# STorM32_NT_BGC_v332m_sz2u.net
KiCad netlist of a schematic drawn in EAGLE
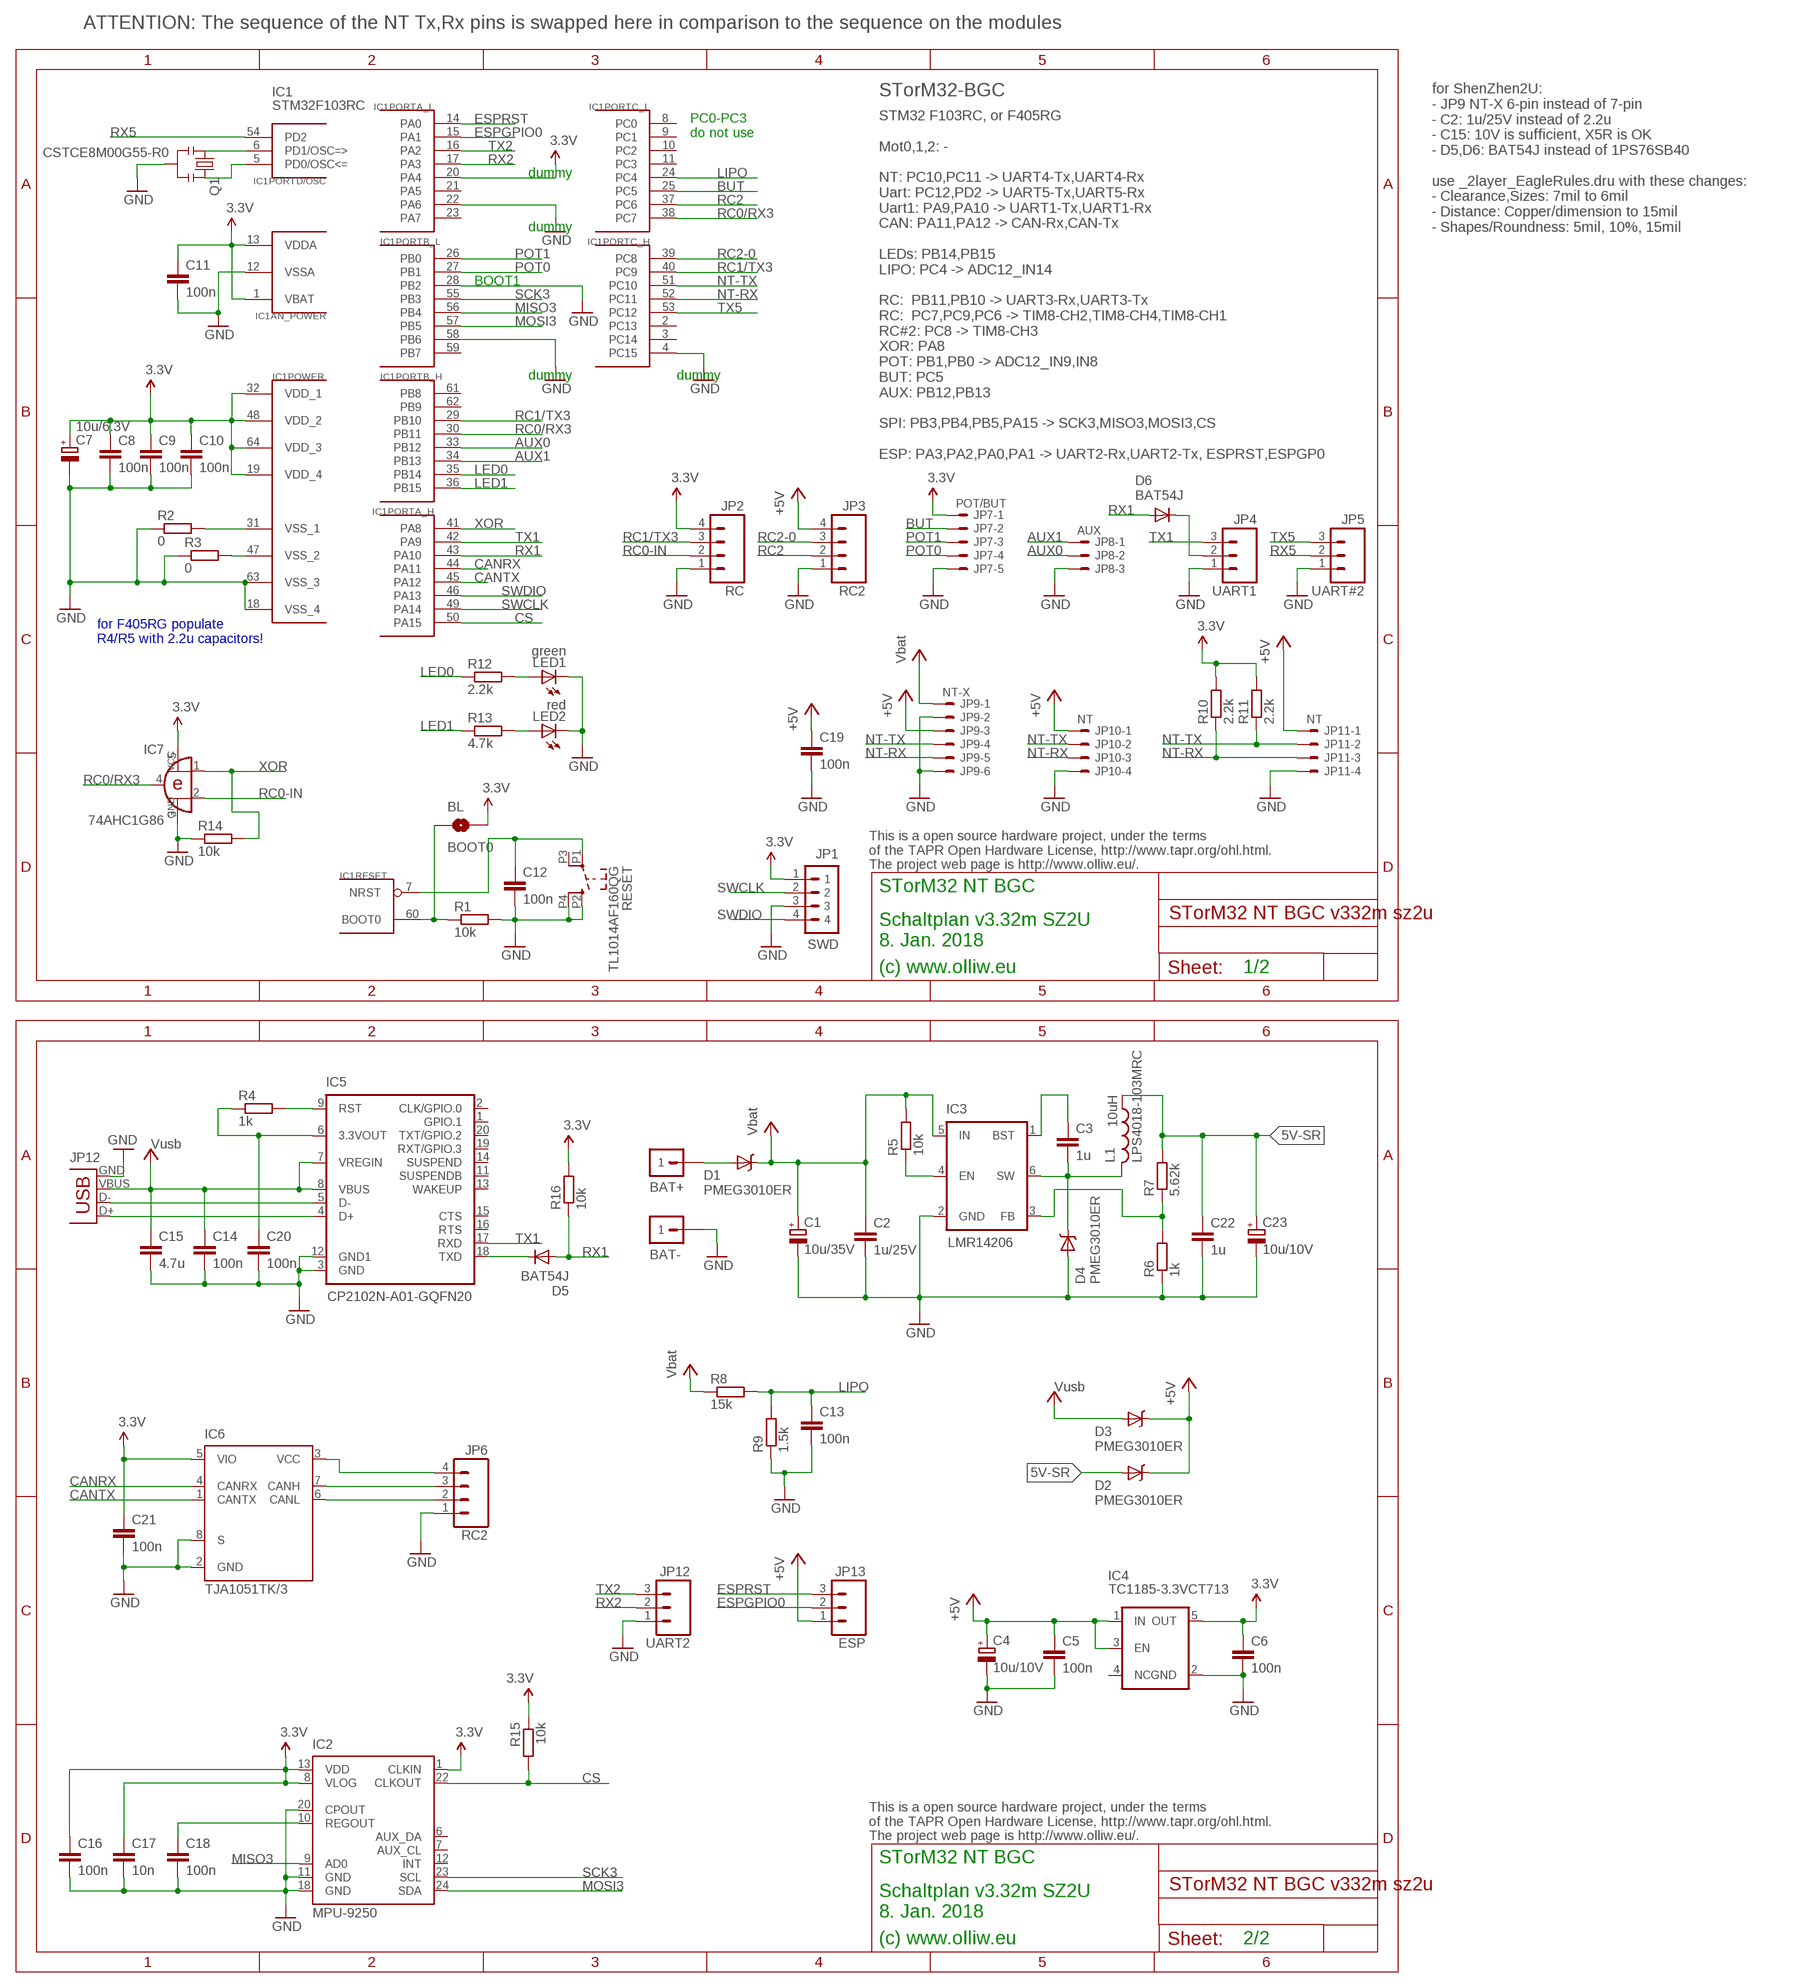
[diagram p0: schematic, sheet 1]

(export (version "E")
  (design (tool "Eeschema 10.0.6"))
  (components
    (comp (ref "BAT+")
      (value "M1X1")
      (footprint "eagle-import:1X1_WITHOUT")
      (libsource (lib "eagle-import") (part "M1X1"))
    )
    (comp (ref "BAT-")
      (value "M1X1")
      (footprint "eagle-import:1X1_WITHOUT")
      (libsource (lib "eagle-import") (part "M1X1"))
    )
    (comp (ref "BL")
      (value "BOOT0")
      (footprint "eagle-import:SJ_2S-NO")
      (libsource (lib "eagle-import") (part "SOLDERJUMPERNO"))
    )
    (comp (ref "C1")
      (value "10u/35V")
      (footprint "eagle-import:SMC_B")
      (libsource (lib "eagle-import") (part "CPOL-EUSMCB"))
    )
    (comp (ref "C2")
      (value "1u/25V")
      (footprint "eagle-import:C0603")
      (libsource (lib "eagle-import") (part "C-EUC0603"))
    )
    (comp (ref "C3")
      (value "1u")
      (footprint "eagle-import:C0603")
      (libsource (lib "eagle-import") (part "C-EUC0603"))
    )
    (comp (ref "C4")
      (value "10u/10V")
      (footprint "eagle-import:SMC_A")
      (libsource (lib "eagle-import") (part "CPOL-EUSMCA"))
    )
    (comp (ref "C5")
      (value "100n")
      (footprint "eagle-import:C0603")
      (libsource (lib "eagle-import") (part "C-EUC0603"))
    )
    (comp (ref "C6")
      (value "100n")
      (footprint "eagle-import:C0402")
      (libsource (lib "eagle-import") (part "C-EUC0402"))
    )
    (comp (ref "C7")
      (value "10u/6.3V")
      (footprint "eagle-import:SMC_A")
      (libsource (lib "eagle-import") (part "CPOL-EUSMCA"))
    )
    (comp (ref "C8")
      (value "100n")
      (footprint "eagle-import:C0402")
      (libsource (lib "eagle-import") (part "C-EUC0402"))
    )
    (comp (ref "C9")
      (value "100n")
      (footprint "eagle-import:C0402")
      (libsource (lib "eagle-import") (part "C-EUC0402"))
    )
    (comp (ref "C10")
      (value "100n")
      (footprint "eagle-import:C0402")
      (libsource (lib "eagle-import") (part "C-EUC0402"))
    )
    (comp (ref "C11")
      (value "100n")
      (footprint "eagle-import:C0402")
      (libsource (lib "eagle-import") (part "C-EUC0402"))
    )
    (comp (ref "C12")
      (value "100n")
      (footprint "eagle-import:C0402")
      (libsource (lib "eagle-import") (part "C-EUC0402"))
    )
    (comp (ref "C13")
      (value "100n")
      (footprint "eagle-import:C0402")
      (libsource (lib "eagle-import") (part "C-EUC0402"))
    )
    (comp (ref "C14")
      (value "100n")
      (footprint "eagle-import:C0402")
      (libsource (lib "eagle-import") (part "C-EUC0402"))
    )
    (comp (ref "C15")
      (value "4.7u")
      (footprint "eagle-import:C0603")
      (libsource (lib "eagle-import") (part "C-EUC0603"))
    )
    (comp (ref "C16")
      (value "100n")
      (footprint "eagle-import:C0402")
      (libsource (lib "eagle-import") (part "C-EUC0402"))
    )
    (comp (ref "C17")
      (value "10n")
      (footprint "eagle-import:C0402")
      (libsource (lib "eagle-import") (part "C-EUC0402"))
    )
    (comp (ref "C18")
      (value "100n")
      (footprint "eagle-import:C0402")
      (libsource (lib "eagle-import") (part "C-EUC0402"))
    )
    (comp (ref "C19")
      (value "100n")
      (footprint "eagle-import:C0402")
      (libsource (lib "eagle-import") (part "C-EUC0402"))
    )
    (comp (ref "C20")
      (value "100n")
      (footprint "eagle-import:C0402")
      (libsource (lib "eagle-import") (part "C-EUC0402"))
    )
    (comp (ref "C21")
      (value "100n")
      (footprint "eagle-import:C0402")
      (libsource (lib "eagle-import") (part "C-EUC0402"))
    )
    (comp (ref "C22")
      (value "1u")
      (footprint "eagle-import:C0603")
      (libsource (lib "eagle-import") (part "C-EUC0603"))
    )
    (comp (ref "C23")
      (value "10u/10V")
      (footprint "eagle-import:SMC_A")
      (libsource (lib "eagle-import") (part "CPOL-EUSMCA"))
    )
    (comp (ref "D1")
      (value "PMEG3010ER")
      (footprint "eagle-import:SOD123W-DIODE")
      (libsource (lib "eagle-import") (part "DIODE-SCHOTTKYSOD123-W"))
    )
    (comp (ref "D2")
      (value "PMEG3010ER")
      (footprint "eagle-import:SOD123W-DIODE")
      (libsource (lib "eagle-import") (part "DIODE-SCHOTTKYSOD123-W"))
    )
    (comp (ref "D3")
      (value "PMEG3010ER")
      (footprint "eagle-import:SOD123W-DIODE")
      (libsource (lib "eagle-import") (part "DIODE-SCHOTTKYSOD123-W"))
    )
    (comp (ref "D4")
      (value "PMEG3010ER")
      (footprint "eagle-import:SOD123W-DIODE")
      (libsource (lib "eagle-import") (part "DIODE-SCHOTTKYSOD123-W"))
    )
    (comp (ref "D5")
      (value "BAT54J")
      (footprint "eagle-import:SOD110-R")
      (libsource (lib "eagle-import") (part "DIODE-SOD110-R"))
    )
    (comp (ref "D6")
      (value "BAT54J")
      (footprint "eagle-import:SOD110-R")
      (libsource (lib "eagle-import") (part "DIODE-SOD110-R"))
    )
    (comp (ref "IC1")
      (value "STM32F103RCT6")
      (footprint "eagle-import:TQFP64")
      (libsource (lib "eagle-import") (part "STM32F10XRXT6"))
    )
    (comp (ref "IC2")
      (value "MPU-9250")
      (footprint "eagle-import:QFN-24-3X3")
      (libsource (lib "eagle-import") (part "IMU3000QFN-24-0.4MIL"))
    )
    (comp (ref "IC3")
      (value "LMR14206")
      (footprint "eagle-import:SOT23-6")
      (libsource (lib "eagle-import") (part "MP2359"))
    )
    (comp (ref "IC4")
      (value "TC1185-3.3VCT713")
      (footprint "eagle-import:SOT23-5")
      (libsource (lib "eagle-import") (part "V_REG_TPS76433SOT23-5"))
    )
    (comp (ref "IC5")
      (value "CP2102N-A01-GQFN20")
      (footprint "eagle-import:QFN20-CP2102N")
      (libsource (lib "eagle-import") (part "CP2102N-QFN20"))
    )
    (comp (ref "IC6")
      (value "TJA1051TK/3")
      (footprint "eagle-import:HVSON8")
      (libsource (lib "eagle-import") (part "TJA1051TK/3"))
    )
    (comp (ref "IC7")
      (value "74AHC1G86")
      (footprint "eagle-import:SOT23-5-VER1")
      (libsource (lib "eagle-import") (part "74AHC1G86"))
    )
    (comp (ref "JP1")
      (value "SWD")
      (footprint "eagle-import:4X1_1P27_OCT_BILEX")
      (libsource (lib "eagle-import") (part "P4X1_1P27-OCT_BILEX"))
    )
    (comp (ref "JP2")
      (value "RC")
      (footprint "eagle-import:1X04_NO_SILK")
      (libsource (lib "eagle-import") (part "M041X04_NO_SILK"))
    )
    (comp (ref "JP3")
      (value "RC2")
      (footprint "eagle-import:1X04_NO_SILK")
      (libsource (lib "eagle-import") (part "M041X04_NO_SILK"))
    )
    (comp (ref "JP4")
      (value "UART1")
      (footprint "eagle-import:1X03_NO_SILK")
      (libsource (lib "eagle-import") (part "M031X03_NO_SILK"))
    )
    (comp (ref "JP5")
      (value "UART#2")
      (footprint "eagle-import:1X03_NO_SILK")
      (libsource (lib "eagle-import") (part "M031X03_NO_SILK"))
    )
    (comp (ref "JP6")
      (value "RC2")
      (footprint "eagle-import:1X04_NO_SILK")
      (libsource (lib "eagle-import") (part "M041X04_NO_SILK"))
    )
    (comp (ref "JP7")
      (value "POT/BUT")
      (footprint "eagle-import:SM05B-SRSS-TB")
      (libsource (lib "eagle-import") (part "?M05B-SRSS-TBS"))
    )
    (comp (ref "JP8")
      (value "AUX")
      (footprint "eagle-import:SM03B-SRSS-TB")
      (libsource (lib "eagle-import") (part "?M03B-SRSS-TBS"))
    )
    (comp (ref "JP9")
      (value "NT-X")
      (footprint "eagle-import:SM06B-SRSS-TB")
      (libsource (lib "eagle-import") (part "?M06B-SRSS-TBS"))
    )
    (comp (ref "JP10")
      (value "NT")
      (footprint "eagle-import:SM04B-SRSS-TB")
      (libsource (lib "eagle-import") (part "?M04B-SRSS-TBS"))
    )
    (comp (ref "JP11")
      (value "NT")
      (footprint "eagle-import:SM04B-SRSS-TB")
      (libsource (lib "eagle-import") (part "?M04B-SRSS-TBS"))
    )
    (comp (ref "JP12")
      (value "UART2")
      (footprint "eagle-import:1X03_NO_SILK")
      (libsource (lib "eagle-import") (part "M031X03_NO_SILK"))
    )
    (comp (ref "JP13")
      (value "ESP")
      (footprint "eagle-import:1X03_NO_SILK")
      (libsource (lib "eagle-import") (part "M031X03_NO_SILK"))
    )
    (comp (ref "L1")
      (value "LPS4018-103MRC")
      (footprint "eagle-import:L4X4")
      (libsource (lib "eagle-import") (part "L"))
    )
    (comp (ref "LED1")
      (value "green")
      (footprint "eagle-import:CHIPLED_0603")
      (libsource (lib "eagle-import") (part "LEDCHIPLED_0603"))
    )
    (comp (ref "LED2")
      (value "red")
      (footprint "eagle-import:CHIPLED_0603")
      (libsource (lib "eagle-import") (part "LEDCHIPLED_0603"))
    )
    (comp (ref "Q1")
      (value "CSTCE8M00G55-R0")
      (footprint "eagle-import:RESONATOR-SMD")
      (libsource (lib "eagle-import") (part "RESONATORSMD"))
    )
    (comp (ref "R1")
      (value "10k")
      (footprint "eagle-import:R0402")
      (libsource (lib "eagle-import") (part "R-EU_R0402"))
    )
    (comp (ref "R2")
      (value "0")
      (footprint "eagle-import:R0402")
      (libsource (lib "eagle-import") (part "R-EU_R0402"))
    )
    (comp (ref "R3")
      (value "0")
      (footprint "eagle-import:R0402")
      (libsource (lib "eagle-import") (part "R-EU_R0402"))
    )
    (comp (ref "R4")
      (value "1k")
      (footprint "eagle-import:R0402")
      (libsource (lib "eagle-import") (part "R-EU_R0402"))
    )
    (comp (ref "R5")
      (value "10k")
      (footprint "eagle-import:R0402")
      (libsource (lib "eagle-import") (part "R-EU_R0402"))
    )
    (comp (ref "R6")
      (value "1k")
      (footprint "eagle-import:R0402")
      (libsource (lib "eagle-import") (part "R-EU_R0402"))
    )
    (comp (ref "R7")
      (value "5.62k")
      (footprint "eagle-import:R0402")
      (libsource (lib "eagle-import") (part "R-EU_R0402"))
    )
    (comp (ref "R8")
      (value "15k")
      (footprint "eagle-import:R0402")
      (libsource (lib "eagle-import") (part "R-EU_R0402"))
    )
    (comp (ref "R9")
      (value "1.5k")
      (footprint "eagle-import:R0402")
      (libsource (lib "eagle-import") (part "R-EU_R0402"))
    )
    (comp (ref "R10")
      (value "2.2k")
      (footprint "eagle-import:R0402")
      (libsource (lib "eagle-import") (part "R-EU_R0402"))
    )
    (comp (ref "R11")
      (value "2.2k")
      (footprint "eagle-import:R0402")
      (libsource (lib "eagle-import") (part "R-EU_R0402"))
    )
    (comp (ref "R12")
      (value "2.2k")
      (footprint "eagle-import:R0402")
      (libsource (lib "eagle-import") (part "R-EU_R0402"))
    )
    (comp (ref "R13")
      (value "4.7k")
      (footprint "eagle-import:R0402")
      (libsource (lib "eagle-import") (part "R-EU_R0402"))
    )
    (comp (ref "R14")
      (value "10k")
      (footprint "eagle-import:R0402")
      (libsource (lib "eagle-import") (part "R-EU_R0402"))
    )
    (comp (ref "R15")
      (value "10k")
      (footprint "eagle-import:R0402")
      (libsource (lib "eagle-import") (part "R-EU_R0402"))
    )
    (comp (ref "R16")
      (value "10k")
      (footprint "eagle-import:R0402")
      (libsource (lib "eagle-import") (part "R-EU_R0402"))
    )
    (comp (ref "RESET")
      (value "TL1014AF160QG")
      (footprint "eagle-import:TACTILE-SWITCH-SMD-RIGHT-TL1014")
      (libsource (lib "eagle-import") (part "SWITCH-SMD-RIGHT-TL1014"))
    )
    (comp (ref "USB")
      (value "Amphenol 10118192-0001LF")
      (footprint "eagle-import:USB-MICROB")
      (libsource (lib "eagle-import") (part "USB-MICROB"))
    )
  )
  (nets
    (net (code "1") (name "+5V") (class "Default")
      (node (ref "C19") (pin "1") (pinfunction "1_1") (pintype "passive"))
      (node (ref "C4") (pin "+") (pinfunction "+_+") (pintype "passive"))
      (node (ref "C5") (pin "1") (pinfunction "1_1") (pintype "passive"))
      (node (ref "D2") (pin "C") (pinfunction "C_C") (pintype "passive"))
      (node (ref "D3") (pin "C") (pinfunction "C_C") (pintype "passive"))
      (node (ref "IC4") (pin "1") (pinfunction "IN_1") (pintype "power_in"))
      (node (ref "IC4") (pin "3") (pinfunction "EN_3") (pintype "input"))
      (node (ref "JP10") (pin "1") (pinfunction "S_1") (pintype "passive"))
      (node (ref "JP11") (pin "1") (pinfunction "S_1") (pintype "passive"))
      (node (ref "JP13") (pin "1") (pinfunction "1_1") (pintype "passive"))
      (node (ref "JP3") (pin "4") (pinfunction "4_4") (pintype "passive"))
      (node (ref "JP9") (pin "3") (pinfunction "S_3") (pintype "passive"))
    )
    (net (code "2") (name "/AUX0") (class "Default")
      (node (ref "IC1") (pin "33") (pinfunction "PB12_33") (pintype "bidirectional"))
      (node (ref "JP8") (pin "2") (pinfunction "S_2") (pintype "passive"))
    )
    (net (code "3") (name "/AUX1") (class "Default")
      (node (ref "IC1") (pin "34") (pinfunction "PB13_34") (pintype "bidirectional"))
      (node (ref "JP8") (pin "1") (pinfunction "S_1") (pintype "passive"))
    )
    (net (code "4") (name "/BUT") (class "Default")
      (node (ref "IC1") (pin "25") (pinfunction "PC5_25") (pintype "bidirectional"))
      (node (ref "JP7") (pin "2") (pinfunction "S_2") (pintype "passive"))
    )
    (net (code "5") (name "/CANRX") (class "Default")
      (node (ref "IC1") (pin "44") (pinfunction "PA11_44") (pintype "bidirectional"))
      (node (ref "IC6") (pin "4") (pinfunction "CANRX_4") (pintype "output"))
    )
    (net (code "6") (name "/CANTX") (class "Default")
      (node (ref "IC1") (pin "45") (pinfunction "PA12_45") (pintype "bidirectional"))
      (node (ref "IC6") (pin "1") (pinfunction "CANTX_1") (pintype "input"))
    )
    (net (code "7") (name "/CS") (class "Default")
      (node (ref "IC1") (pin "50") (pinfunction "PA15_50") (pintype "bidirectional"))
      (node (ref "IC2") (pin "22") (pinfunction "CLKOUT_22") (pintype "bidirectional"))
      (node (ref "R15") (pin "2") (pinfunction "2_2") (pintype "passive"))
    )
    (net (code "8") (name "/ESPGPIO0") (class "Default")
      (node (ref "IC1") (pin "15") (pinfunction "PA1_15") (pintype "bidirectional"))
      (node (ref "JP13") (pin "2") (pinfunction "2_2") (pintype "passive"))
    )
    (net (code "9") (name "/ESPRST") (class "Default")
      (node (ref "IC1") (pin "14") (pinfunction "PA0_14") (pintype "bidirectional"))
      (node (ref "JP13") (pin "3") (pinfunction "3_3") (pintype "passive"))
    )
    (net (code "10") (name "/LED0") (class "Default")
      (node (ref "IC1") (pin "35") (pinfunction "PB14_35") (pintype "bidirectional"))
      (node (ref "R12") (pin "1") (pinfunction "1_1") (pintype "passive"))
    )
    (net (code "11") (name "/LED1") (class "Default")
      (node (ref "IC1") (pin "36") (pinfunction "PB15_36") (pintype "bidirectional"))
      (node (ref "R13") (pin "1") (pinfunction "1_1") (pintype "passive"))
    )
    (net (code "12") (name "/LIPO") (class "Default")
      (node (ref "C13") (pin "1") (pinfunction "1_1") (pintype "passive"))
      (node (ref "IC1") (pin "24") (pinfunction "PC4_24") (pintype "bidirectional"))
      (node (ref "R8") (pin "2") (pinfunction "2_2") (pintype "passive"))
      (node (ref "R9") (pin "2") (pinfunction "2_2") (pintype "passive"))
    )
    (net (code "13") (name "/MISO3") (class "Default")
      (node (ref "IC1") (pin "56") (pinfunction "PB4_56") (pintype "bidirectional"))
      (node (ref "IC2") (pin "9") (pinfunction "AD0_9") (pintype "bidirectional"))
    )
    (net (code "14") (name "/MOSI3") (class "Default")
      (node (ref "IC1") (pin "57") (pinfunction "PB5_57") (pintype "bidirectional"))
      (node (ref "IC2") (pin "24") (pinfunction "SDA_24") (pintype "bidirectional"))
    )
    (net (code "15") (name "/NT-RX") (class "Default")
      (node (ref "IC1") (pin "52") (pinfunction "PC11_52") (pintype "bidirectional"))
      (node (ref "JP10") (pin "3") (pinfunction "S_3") (pintype "passive"))
      (node (ref "JP11") (pin "3") (pinfunction "S_3") (pintype "passive"))
      (node (ref "JP9") (pin "5") (pinfunction "S_5") (pintype "passive"))
      (node (ref "R10") (pin "1") (pinfunction "1_1") (pintype "passive"))
    )
    (net (code "16") (name "/NT-TX") (class "Default")
      (node (ref "IC1") (pin "51") (pinfunction "PC10_51") (pintype "bidirectional"))
      (node (ref "JP10") (pin "2") (pinfunction "S_2") (pintype "passive"))
      (node (ref "JP11") (pin "2") (pinfunction "S_2") (pintype "passive"))
      (node (ref "JP9") (pin "4") (pinfunction "S_4") (pintype "passive"))
      (node (ref "R11") (pin "1") (pinfunction "1_1") (pintype "passive"))
    )
    (net (code "17") (name "/POT0") (class "Default")
      (node (ref "IC1") (pin "27") (pinfunction "PB1_27") (pintype "bidirectional"))
      (node (ref "JP7") (pin "4") (pinfunction "S_4") (pintype "passive"))
    )
    (net (code "18") (name "/POT1") (class "Default")
      (node (ref "IC1") (pin "26") (pinfunction "PB0_26") (pintype "bidirectional"))
      (node (ref "JP7") (pin "3") (pinfunction "S_3") (pintype "passive"))
    )
    (net (code "19") (name "/RC0-IN") (class "Default")
      (node (ref "IC7") (pin "2") (pinfunction "I1_2") (pintype "input"))
      (node (ref "JP2") (pin "2") (pinfunction "2_2") (pintype "passive"))
    )
    (net (code "20") (name "/RC0{slash}RX3") (class "Default")
      (node (ref "IC1") (pin "30") (pinfunction "PB11_30") (pintype "bidirectional"))
      (node (ref "IC1") (pin "38") (pinfunction "PC7_38") (pintype "bidirectional"))
      (node (ref "IC7") (pin "4") (pinfunction "O_4") (pintype "output"))
    )
    (net (code "21") (name "/RC1{slash}TX3") (class "Default")
      (node (ref "IC1") (pin "29") (pinfunction "PB10_29") (pintype "bidirectional"))
      (node (ref "IC1") (pin "40") (pinfunction "PC9_40") (pintype "bidirectional"))
      (node (ref "JP2") (pin "3") (pinfunction "3_3") (pintype "passive"))
    )
    (net (code "22") (name "/RC2") (class "Default")
      (node (ref "IC1") (pin "37") (pinfunction "PC6_37") (pintype "bidirectional"))
      (node (ref "JP3") (pin "2") (pinfunction "2_2") (pintype "passive"))
    )
    (net (code "23") (name "/RC2-0") (class "Default")
      (node (ref "IC1") (pin "39") (pinfunction "PC8_39") (pintype "bidirectional"))
      (node (ref "JP3") (pin "3") (pinfunction "3_3") (pintype "passive"))
    )
    (net (code "24") (name "/RX1") (class "Default")
      (node (ref "D5") (pin "A") (pinfunction "A_A") (pintype "passive"))
      (node (ref "D6") (pin "A") (pinfunction "A_A") (pintype "passive"))
      (node (ref "IC1") (pin "43") (pinfunction "PA10_43") (pintype "bidirectional"))
      (node (ref "R16") (pin "1") (pinfunction "1_1") (pintype "passive"))
    )
    (net (code "25") (name "/RX2") (class "Default")
      (node (ref "IC1") (pin "17") (pinfunction "PA3_17") (pintype "bidirectional"))
      (node (ref "JP12") (pin "2") (pinfunction "2_2") (pintype "passive"))
    )
    (net (code "26") (name "/RX5") (class "Default")
      (node (ref "IC1") (pin "54") (pinfunction "PD2_54") (pintype "bidirectional"))
      (node (ref "JP5") (pin "2") (pinfunction "2_2") (pintype "passive"))
    )
    (net (code "27") (name "/SCK3") (class "Default")
      (node (ref "IC1") (pin "55") (pinfunction "PB3_55") (pintype "bidirectional"))
      (node (ref "IC2") (pin "23") (pinfunction "SCL_23") (pintype "bidirectional"))
    )
    (net (code "28") (name "/SWCLK") (class "Default")
      (node (ref "IC1") (pin "49") (pinfunction "PA14_49") (pintype "bidirectional"))
      (node (ref "JP1") (pin "2") (pinfunction "2_2") (pintype "passive"))
    )
    (net (code "29") (name "/SWDIO") (class "Default")
      (node (ref "IC1") (pin "46") (pinfunction "PA13_46") (pintype "bidirectional"))
      (node (ref "JP1") (pin "4") (pinfunction "4_4") (pintype "passive"))
    )
    (net (code "30") (name "/TX1") (class "Default")
      (node (ref "IC1") (pin "42") (pinfunction "PA9_42") (pintype "bidirectional"))
      (node (ref "IC5") (pin "17") (pinfunction "RXD_17") (pintype "input"))
      (node (ref "JP4") (pin "3") (pinfunction "3_3") (pintype "passive"))
    )
    (net (code "31") (name "/TX2") (class "Default")
      (node (ref "IC1") (pin "16") (pinfunction "PA2_16") (pintype "bidirectional"))
      (node (ref "JP12") (pin "3") (pinfunction "3_3") (pintype "passive"))
    )
    (net (code "32") (name "/TX5") (class "Default")
      (node (ref "IC1") (pin "53") (pinfunction "PC12_53") (pintype "bidirectional"))
      (node (ref "JP5") (pin "3") (pinfunction "3_3") (pintype "passive"))
    )
    (net (code "33") (name "/XOR") (class "Default")
      (node (ref "IC1") (pin "41") (pinfunction "PA8_41") (pintype "bidirectional"))
      (node (ref "IC7") (pin "1") (pinfunction "I0_1") (pintype "input"))
      (node (ref "R14") (pin "2") (pinfunction "2_2") (pintype "passive"))
    )
    (net (code "34") (name "3.3V") (class "Default")
      (node (ref "BL") (pin "2") (pinfunction "2_2") (pintype "passive"))
      (node (ref "C10") (pin "1") (pinfunction "1_1") (pintype "passive"))
      (node (ref "C11") (pin "1") (pinfunction "1_1") (pintype "passive"))
      (node (ref "C16") (pin "1") (pinfunction "1_1") (pintype "passive"))
      (node (ref "C17") (pin "1") (pinfunction "1_1") (pintype "passive"))
      (node (ref "C21") (pin "1") (pinfunction "1_1") (pintype "passive"))
      (node (ref "C6") (pin "1") (pinfunction "1_1") (pintype "passive"))
      (node (ref "C7") (pin "+") (pinfunction "+_+") (pintype "passive"))
      (node (ref "C8") (pin "1") (pinfunction "1_1") (pintype "passive"))
      (node (ref "C9") (pin "1") (pinfunction "1_1") (pintype "passive"))
      (node (ref "IC1") (pin "1") (pinfunction "VBAT_1") (pintype "power_in"))
      (node (ref "IC1") (pin "13") (pinfunction "VDDA_13") (pintype "power_in"))
      (node (ref "IC1") (pin "19") (pinfunction "VDD_4_19") (pintype "power_in"))
      (node (ref "IC1") (pin "20") (pinfunction "PA4_20") (pintype "bidirectional"))
      (node (ref "IC1") (pin "32") (pinfunction "VDD_1_32") (pintype "power_in"))
      (node (ref "IC1") (pin "48") (pinfunction "VDD_2_48") (pintype "power_in"))
      (node (ref "IC1") (pin "64") (pinfunction "VDD_3_64") (pintype "power_in"))
      (node (ref "IC2") (pin "1") (pinfunction "CLKIN_1") (pintype "bidirectional"))
      (node (ref "IC2") (pin "13") (pinfunction "VDD_13") (pintype "bidirectional"))
      (node (ref "IC2") (pin "8") (pinfunction "VLOG_8") (pintype "bidirectional"))
      (node (ref "IC4") (pin "5") (pinfunction "OUT_5") (pintype "output"))
      (node (ref "IC6") (pin "5") (pinfunction "VIO_5") (pintype "power_in"))
      (node (ref "IC7") (pin "5") (pinfunction "VCC_5") (pintype "power_in"))
      (node (ref "JP1") (pin "1") (pinfunction "1_1") (pintype "passive"))
      (node (ref "JP2") (pin "4") (pinfunction "4_4") (pintype "passive"))
      (node (ref "JP7") (pin "1") (pinfunction "S_1") (pintype "passive"))
      (node (ref "R10") (pin "2") (pinfunction "2_2") (pintype "passive"))
      (node (ref "R11") (pin "2") (pinfunction "2_2") (pintype "passive"))
      (node (ref "R15") (pin "1") (pinfunction "1_1") (pintype "passive"))
      (node (ref "R16") (pin "2") (pinfunction "2_2") (pintype "passive"))
    )
    (net (code "35") (name "5V-SR") (class "Default")
      (node (ref "C22") (pin "1") (pinfunction "1_1") (pintype "passive"))
      (node (ref "C23") (pin "+") (pinfunction "+_+") (pintype "passive"))
      (node (ref "D2") (pin "A") (pinfunction "A_A") (pintype "passive"))
      (node (ref "L1") (pin "1") (pinfunction "1_1") (pintype "passive"))
      (node (ref "R7") (pin "2") (pinfunction "2_2") (pintype "passive"))
    )
    (net (code "36") (name "GND") (class "Default")
      (node (ref "BAT-") (pin "1") (pinfunction "1_1") (pintype "passive"))
      (node (ref "C1") (pin "-") (pinfunction "-_-") (pintype "passive"))
      (node (ref "C10") (pin "2") (pinfunction "2_2") (pintype "passive"))
      (node (ref "C11") (pin "2") (pinfunction "2_2") (pintype "passive"))
      (node (ref "C12") (pin "2") (pinfunction "2_2") (pintype "passive"))
      (node (ref "C13") (pin "2") (pinfunction "2_2") (pintype "passive"))
      (node (ref "C14") (pin "2") (pinfunction "2_2") (pintype "passive"))
      (node (ref "C15") (pin "2") (pinfunction "2_2") (pintype "passive"))
      (node (ref "C16") (pin "2") (pinfunction "2_2") (pintype "passive"))
      (node (ref "C17") (pin "2") (pinfunction "2_2") (pintype "passive"))
      (node (ref "C18") (pin "2") (pinfunction "2_2") (pintype "passive"))
      (node (ref "C19") (pin "2") (pinfunction "2_2") (pintype "passive"))
      (node (ref "C2") (pin "2") (pinfunction "2_2") (pintype "passive"))
      (node (ref "C20") (pin "2") (pinfunction "2_2") (pintype "passive"))
      (node (ref "C21") (pin "2") (pinfunction "2_2") (pintype "passive"))
      (node (ref "C22") (pin "2") (pinfunction "2_2") (pintype "passive"))
      (node (ref "C23") (pin "-") (pinfunction "-_-") (pintype "passive"))
      (node (ref "C4") (pin "-") (pinfunction "-_-") (pintype "passive"))
      (node (ref "C5") (pin "2") (pinfunction "2_2") (pintype "passive"))
      (node (ref "C6") (pin "2") (pinfunction "2_2") (pintype "passive"))
      (node (ref "C7") (pin "-") (pinfunction "-_-") (pintype "passive"))
      (node (ref "C8") (pin "2") (pinfunction "2_2") (pintype "passive"))
      (node (ref "C9") (pin "2") (pinfunction "2_2") (pintype "passive"))
      (node (ref "D4") (pin "A") (pinfunction "A_A") (pintype "passive"))
      (node (ref "IC1") (pin "12") (pinfunction "VSSA_12") (pintype "power_in"))
      (node (ref "IC1") (pin "18") (pinfunction "VSS_4_18") (pintype "power_in"))
      (node (ref "IC1") (pin "22") (pinfunction "PA6_22") (pintype "bidirectional"))
      (node (ref "IC1") (pin "28") (pinfunction "PB2_28") (pintype "bidirectional"))
      (node (ref "IC1") (pin "4") (pinfunction "PC15_4") (pintype "bidirectional"))
      (node (ref "IC1") (pin "58") (pinfunction "PB6_58") (pintype "bidirectional"))
      (node (ref "IC1") (pin "63") (pinfunction "VSS_3_63") (pintype "power_in"))
      (node (ref "IC2") (pin "11") (pinfunction "GND_11") (pintype "bidirectional"))
      (node (ref "IC2") (pin "18") (pinfunction "GND_18") (pintype "bidirectional"))
      (node (ref "IC2") (pin "20") (pinfunction "CPOUT_20") (pintype "bidirectional"))
      (node (ref "IC3") (pin "2") (pinfunction "GND_2") (pintype "power_in"))
      (node (ref "IC4") (pin "2") (pinfunction "GND_2") (pintype "power_in"))
      (node (ref "IC5") (pin "12") (pinfunction "GND1_12") (pintype "power_in"))
      (node (ref "IC5") (pin "3") (pinfunction "GND_3") (pintype "power_in"))
      (node (ref "IC6") (pin "2") (pinfunction "GND_2") (pintype "power_in"))
      (node (ref "IC6") (pin "8") (pinfunction "S_8") (pintype "input"))
      (node (ref "IC7") (pin "3") (pinfunction "GND_3") (pintype "power_in"))
      (node (ref "JP1") (pin "3") (pinfunction "3_3") (pintype "passive"))
      (node (ref "JP10") (pin "4") (pinfunction "S_4") (pintype "passive"))
      (node (ref "JP11") (pin "4") (pinfunction "S_4") (pintype "passive"))
      (node (ref "JP12") (pin "1") (pinfunction "1_1") (pintype "passive"))
      (node (ref "JP2") (pin "1") (pinfunction "1_1") (pintype "passive"))
      (node (ref "JP3") (pin "1") (pinfunction "1_1") (pintype "passive"))
      (node (ref "JP4") (pin "1") (pinfunction "1_1") (pintype "passive"))
      (node (ref "JP5") (pin "1") (pinfunction "1_1") (pintype "passive"))
      (node (ref "JP6") (pin "1") (pinfunction "1_1") (pintype "passive"))
      (node (ref "JP7") (pin "5") (pinfunction "S_5") (pintype "passive"))
      (node (ref "JP8") (pin "3") (pinfunction "S_3") (pintype "passive"))
      (node (ref "JP9") (pin "2") (pinfunction "S_2") (pintype "passive"))
      (node (ref "JP9") (pin "6") (pinfunction "S_6") (pintype "passive"))
      (node (ref "LED1") (pin "C") (pinfunction "C_C") (pintype "passive"))
      (node (ref "LED2") (pin "C") (pinfunction "C_C") (pintype "passive"))
      (node (ref "Q1") (pin "2") (pinfunction "2_2") (pintype "passive"))
      (node (ref "R1") (pin "2") (pinfunction "2_2") (pintype "passive"))
      (node (ref "R14") (pin "1") (pinfunction "1_1") (pintype "passive"))
      (node (ref "R2") (pin "1") (pinfunction "1_1") (pintype "passive"))
      (node (ref "R3") (pin "1") (pinfunction "1_1") (pintype "passive"))
      (node (ref "R6") (pin "1") (pinfunction "1_1") (pintype "passive"))
      (node (ref "R9") (pin "1") (pinfunction "1_1") (pintype "passive"))
      (node (ref "RESET") (pin "P2") (pinfunction "1_P2") (pintype "passive"))
      (node (ref "RESET") (pin "P4") (pinfunction "2_P4") (pintype "passive"))
      (node (ref "USB") (pin "GND") (pinfunction "GND_GND") (pintype "bidirectional"))
    )
    (net (code "37") (name "Net-(BAT+-Pad1)") (class "Default")
      (node (ref "BAT+") (pin "1") (pinfunction "1_1") (pintype "passive"))
      (node (ref "D1") (pin "A") (pinfunction "A_A") (pintype "passive"))
    )
    (net (code "38") (name "Net-(D6-PadC)") (class "Default")
      (node (ref "D6") (pin "C") (pinfunction "C_C") (pintype "passive"))
      (node (ref "JP4") (pin "2") (pinfunction "2_2") (pintype "passive"))
    )
    (net (code "39") (name "Net-(IC1H-PD0{slash}OSC<=)") (class "Default")
      (node (ref "IC1") (pin "5") (pinfunction "PD0/OSC<=_5") (pintype "bidirectional"))
      (node (ref "Q1") (pin "3") (pinfunction "3_3") (pintype "passive"))
    )
    (net (code "40") (name "Net-(IC1H-PD1{slash}OSC=>)") (class "Default")
      (node (ref "IC1") (pin "6") (pinfunction "PD1/OSC=>_6") (pintype "bidirectional"))
      (node (ref "Q1") (pin "1") (pinfunction "1_1") (pintype "passive"))
    )
    (net (code "41") (name "Net-(IC1I-VSS_1)") (class "Default")
      (node (ref "IC1") (pin "31") (pinfunction "VSS_1_31") (pintype "power_in"))
      (node (ref "R2") (pin "2") (pinfunction "2_2") (pintype "passive"))
    )
    (net (code "42") (name "Net-(IC1I-VSS_2)") (class "Default")
      (node (ref "IC1") (pin "47") (pinfunction "VSS_2_47") (pintype "power_in"))
      (node (ref "R3") (pin "2") (pinfunction "2_2") (pintype "passive"))
    )
    (net (code "43") (name "Net-(IC1J-BOOT0)") (class "Default")
      (node (ref "BL") (pin "1") (pinfunction "1_1") (pintype "passive"))
      (node (ref "IC1") (pin "60") (pinfunction "BOOT0_60") (pintype "input"))
      (node (ref "R1") (pin "1") (pinfunction "1_1") (pintype "passive"))
    )
    (net (code "44") (name "Net-(IC1J-NRST)") (class "Default")
      (node (ref "C12") (pin "1") (pinfunction "1_1") (pintype "passive"))
      (node (ref "IC1") (pin "7") (pinfunction "NRST_7") (pintype "input"))
      (node (ref "RESET") (pin "P1") (pinfunction "3_P1") (pintype "passive"))
    )
    (net (code "45") (name "Net-(IC2-REGOUT)") (class "Default")
      (node (ref "C18") (pin "1") (pinfunction "1_1") (pintype "passive"))
      (node (ref "IC2") (pin "10") (pinfunction "REGOUT_10") (pintype "bidirectional"))
    )
    (net (code "46") (name "Net-(IC3-BST)") (class "Default")
      (node (ref "C3") (pin "1") (pinfunction "1_1") (pintype "passive"))
      (node (ref "IC3") (pin "1") (pinfunction "BST_1") (pintype "output"))
    )
    (net (code "47") (name "Net-(IC3-EN)") (class "Default")
      (node (ref "IC3") (pin "4") (pinfunction "EN_4") (pintype "input"))
      (node (ref "R5") (pin "1") (pinfunction "1_1") (pintype "passive"))
    )
    (net (code "48") (name "Net-(IC3-FB)") (class "Default")
      (node (ref "IC3") (pin "3") (pinfunction "FB_3") (pintype "input"))
      (node (ref "R6") (pin "2") (pinfunction "2_2") (pintype "passive"))
      (node (ref "R7") (pin "1") (pinfunction "1_1") (pintype "passive"))
    )
    (net (code "49") (name "Net-(IC3-SW)") (class "Default")
      (node (ref "C3") (pin "2") (pinfunction "2_2") (pintype "passive"))
      (node (ref "D4") (pin "C") (pinfunction "C_C") (pintype "passive"))
      (node (ref "IC3") (pin "6") (pinfunction "SW_6") (pintype "output"))
      (node (ref "L1") (pin "2") (pinfunction "2_2") (pintype "passive"))
    )
    (net (code "50") (name "Net-(IC5-3.3VOUT)") (class "Default")
      (node (ref "C20") (pin "1") (pinfunction "1_1") (pintype "passive"))
      (node (ref "IC5") (pin "6") (pinfunction "3.3VOUT_6") (pintype "power_in"))
      (node (ref "R4") (pin "1") (pinfunction "1_1") (pintype "passive"))
    )
    (net (code "51") (name "Net-(IC5-D+)") (class "Default")
      (node (ref "IC5") (pin "4") (pinfunction "D+_4") (pintype "bidirectional"))
      (node (ref "USB") (pin "D+") (pinfunction "D+_D+") (pintype "bidirectional"))
    )
    (net (code "52") (name "Net-(IC5-D-)") (class "Default")
      (node (ref "IC5") (pin "5") (pinfunction "D-_5") (pintype "bidirectional"))
      (node (ref "USB") (pin "D-") (pinfunction "D-_D-") (pintype "bidirectional"))
    )
    (net (code "53") (name "Net-(IC5-RST)") (class "Default")
      (node (ref "IC5") (pin "9") (pinfunction "RST_9") (pintype "input"))
      (node (ref "R4") (pin "2") (pinfunction "2_2") (pintype "passive"))
    )
    (net (code "54") (name "Net-(IC5-TXD)") (class "Default")
      (node (ref "D5") (pin "C") (pinfunction "C_C") (pintype "passive"))
      (node (ref "IC5") (pin "18") (pinfunction "TXD_18") (pintype "output"))
    )
    (net (code "55") (name "Net-(IC6-CANH)") (class "Default")
      (node (ref "IC6") (pin "7") (pinfunction "CANH_7") (pintype "bidirectional"))
      (node (ref "JP6") (pin "3") (pinfunction "3_3") (pintype "passive"))
    )
    (net (code "56") (name "Net-(IC6-CANL)") (class "Default")
      (node (ref "IC6") (pin "6") (pinfunction "CANL_6") (pintype "bidirectional"))
      (node (ref "JP6") (pin "2") (pinfunction "2_2") (pintype "passive"))
    )
    (net (code "57") (name "Net-(IC6-VCC)") (class "Default")
      (node (ref "IC6") (pin "3") (pinfunction "VCC_3") (pintype "power_in"))
      (node (ref "JP6") (pin "4") (pinfunction "4_4") (pintype "passive"))
    )
    (net (code "58") (name "Net-(LED1-PadA)") (class "Default")
      (node (ref "LED1") (pin "A") (pinfunction "A_A") (pintype "passive"))
      (node (ref "R12") (pin "2") (pinfunction "2_2") (pintype "passive"))
    )
    (net (code "59") (name "Net-(LED2-PadA)") (class "Default")
      (node (ref "LED2") (pin "A") (pinfunction "A_A") (pintype "passive"))
      (node (ref "R13") (pin "2") (pinfunction "2_2") (pintype "passive"))
    )
    (net (code "60") (name "Vbat") (class "Default")
      (node (ref "C1") (pin "+") (pinfunction "+_+") (pintype "passive"))
      (node (ref "C2") (pin "1") (pinfunction "1_1") (pintype "passive"))
      (node (ref "D1") (pin "C") (pinfunction "C_C") (pintype "passive"))
      (node (ref "IC3") (pin "5") (pinfunction "IN_5") (pintype "power_in"))
      (node (ref "JP9") (pin "1") (pinfunction "S_1") (pintype "passive"))
      (node (ref "R5") (pin "2") (pinfunction "2_2") (pintype "passive"))
      (node (ref "R8") (pin "1") (pinfunction "1_1") (pintype "passive"))
    )
    (net (code "61") (name "Vusb") (class "Default")
      (node (ref "C14") (pin "1") (pinfunction "1_1") (pintype "passive"))
      (node (ref "C15") (pin "1") (pinfunction "1_1") (pintype "passive"))
      (node (ref "D3") (pin "A") (pinfunction "A_A") (pintype "passive"))
      (node (ref "IC5") (pin "7") (pinfunction "VREGIN_7") (pintype "power_in"))
      (node (ref "IC5") (pin "8") (pinfunction "VBUS_8") (pintype "input"))
      (node (ref "USB") (pin "VBUS") (pinfunction "VBUS_VBUS") (pintype "bidirectional"))
    )
    (net (code "62") (name "unconnected-(IC1C-PA5-Pad21)") (class "Default")
      (node (ref "IC1") (pin "21") (pinfunction "PA5_21") (pintype "bidirectional"))
    )
    (net (code "63") (name "unconnected-(IC1C-PA7-Pad23)") (class "Default")
      (node (ref "IC1") (pin "23") (pinfunction "PA7_23") (pintype "bidirectional"))
    )
    (net (code "64") (name "unconnected-(IC1D-PB8-Pad61)") (class "Default")
      (node (ref "IC1") (pin "61") (pinfunction "PB8_61") (pintype "bidirectional"))
    )
    (net (code "65") (name "unconnected-(IC1D-PB9-Pad62)") (class "Default")
      (node (ref "IC1") (pin "62") (pinfunction "PB9_62") (pintype "bidirectional"))
    )
    (net (code "66") (name "unconnected-(IC1E-PB7-Pad59)") (class "Default")
      (node (ref "IC1") (pin "59") (pinfunction "PB7_59") (pintype "bidirectional"))
    )
    (net (code "67") (name "unconnected-(IC1F-PC13-Pad2)") (class "Default")
      (node (ref "IC1") (pin "2") (pinfunction "PC13_2") (pintype "bidirectional"))
    )
    (net (code "68") (name "unconnected-(IC1F-PC14-Pad3)") (class "Default")
      (node (ref "IC1") (pin "3") (pinfunction "PC14_3") (pintype "bidirectional"))
    )
    (net (code "69") (name "unconnected-(IC1G-PC0-Pad8)") (class "Default")
      (node (ref "IC1") (pin "8") (pinfunction "PC0_8") (pintype "bidirectional"))
    )
    (net (code "70") (name "unconnected-(IC1G-PC1-Pad9)") (class "Default")
      (node (ref "IC1") (pin "9") (pinfunction "PC1_9") (pintype "bidirectional"))
    )
    (net (code "71") (name "unconnected-(IC1G-PC2-Pad10)") (class "Default")
      (node (ref "IC1") (pin "10") (pinfunction "PC2_10") (pintype "bidirectional"))
    )
    (net (code "72") (name "unconnected-(IC1G-PC3-Pad11)") (class "Default")
      (node (ref "IC1") (pin "11") (pinfunction "PC3_11") (pintype "bidirectional"))
    )
    (net (code "73") (name "unconnected-(IC2-AUX_CL-Pad7)") (class "Default")
      (node (ref "IC2") (pin "7") (pinfunction "AUX_CL_7") (pintype "bidirectional"))
    )
    (net (code "74") (name "unconnected-(IC2-AUX_DA-Pad6)") (class "Default")
      (node (ref "IC2") (pin "6") (pinfunction "AUX_DA_6") (pintype "bidirectional"))
    )
    (net (code "75") (name "unconnected-(IC2-INT-Pad12)") (class "Default")
      (node (ref "IC2") (pin "12") (pinfunction "INT_12") (pintype "bidirectional"))
    )
    (net (code "76") (name "unconnected-(IC4-NC-Pad4)") (class "Default")
      (node (ref "IC4") (pin "4") (pinfunction "NC_4") (pintype "passive"))
    )
    (net (code "77") (name "unconnected-(IC5-CLK{slash}GPIO.0-Pad2)") (class "Default")
      (node (ref "IC5") (pin "2") (pinfunction "CLK/GPIO.0_2") (pintype "bidirectional"))
    )
    (net (code "78") (name "unconnected-(IC5-CTS-Pad15)") (class "Default")
      (node (ref "IC5") (pin "15") (pinfunction "CTS_15") (pintype "input"))
    )
    (net (code "79") (name "unconnected-(IC5-GPIO.1-Pad1)") (class "Default")
      (node (ref "IC5") (pin "1") (pinfunction "GPIO.1_1") (pintype "bidirectional"))
    )
    (net (code "80") (name "unconnected-(IC5-RTS-Pad16)") (class "Default")
      (node (ref "IC5") (pin "16") (pinfunction "RTS_16") (pintype "output"))
    )
    (net (code "81") (name "unconnected-(IC5-RXT{slash}GPIO.3-Pad19)") (class "Default")
      (node (ref "IC5") (pin "19") (pinfunction "RXT/GPIO.3_19") (pintype "bidirectional"))
    )
    (net (code "82") (name "unconnected-(IC5-SUSPEND-Pad14)") (class "Default")
      (node (ref "IC5") (pin "14") (pinfunction "SUSPEND_14") (pintype "output"))
    )
    (net (code "83") (name "unconnected-(IC5-SUSPENDB-Pad11)") (class "Default")
      (node (ref "IC5") (pin "11") (pinfunction "SUSPENDB_11") (pintype "output"))
    )
    (net (code "84") (name "unconnected-(IC5-TXT{slash}GPIO.2-Pad20)") (class "Default")
      (node (ref "IC5") (pin "20") (pinfunction "TXT/GPIO.2_20") (pintype "bidirectional"))
    )
    (net (code "85") (name "unconnected-(IC5-WAKEUP-Pad13)") (class "Default")
      (node (ref "IC5") (pin "13") (pinfunction "WAKEUP_13") (pintype "input"))
    )
    (net (code "86") (name "unconnected-(RESET-4-PadP3)") (class "Default")
      (node (ref "RESET") (pin "P3") (pinfunction "4_P3") (pintype "passive"))
    )
  )
)
